# Power_Controller_2_0.net
KiCad netlist of a schematic drawn in EAGLE
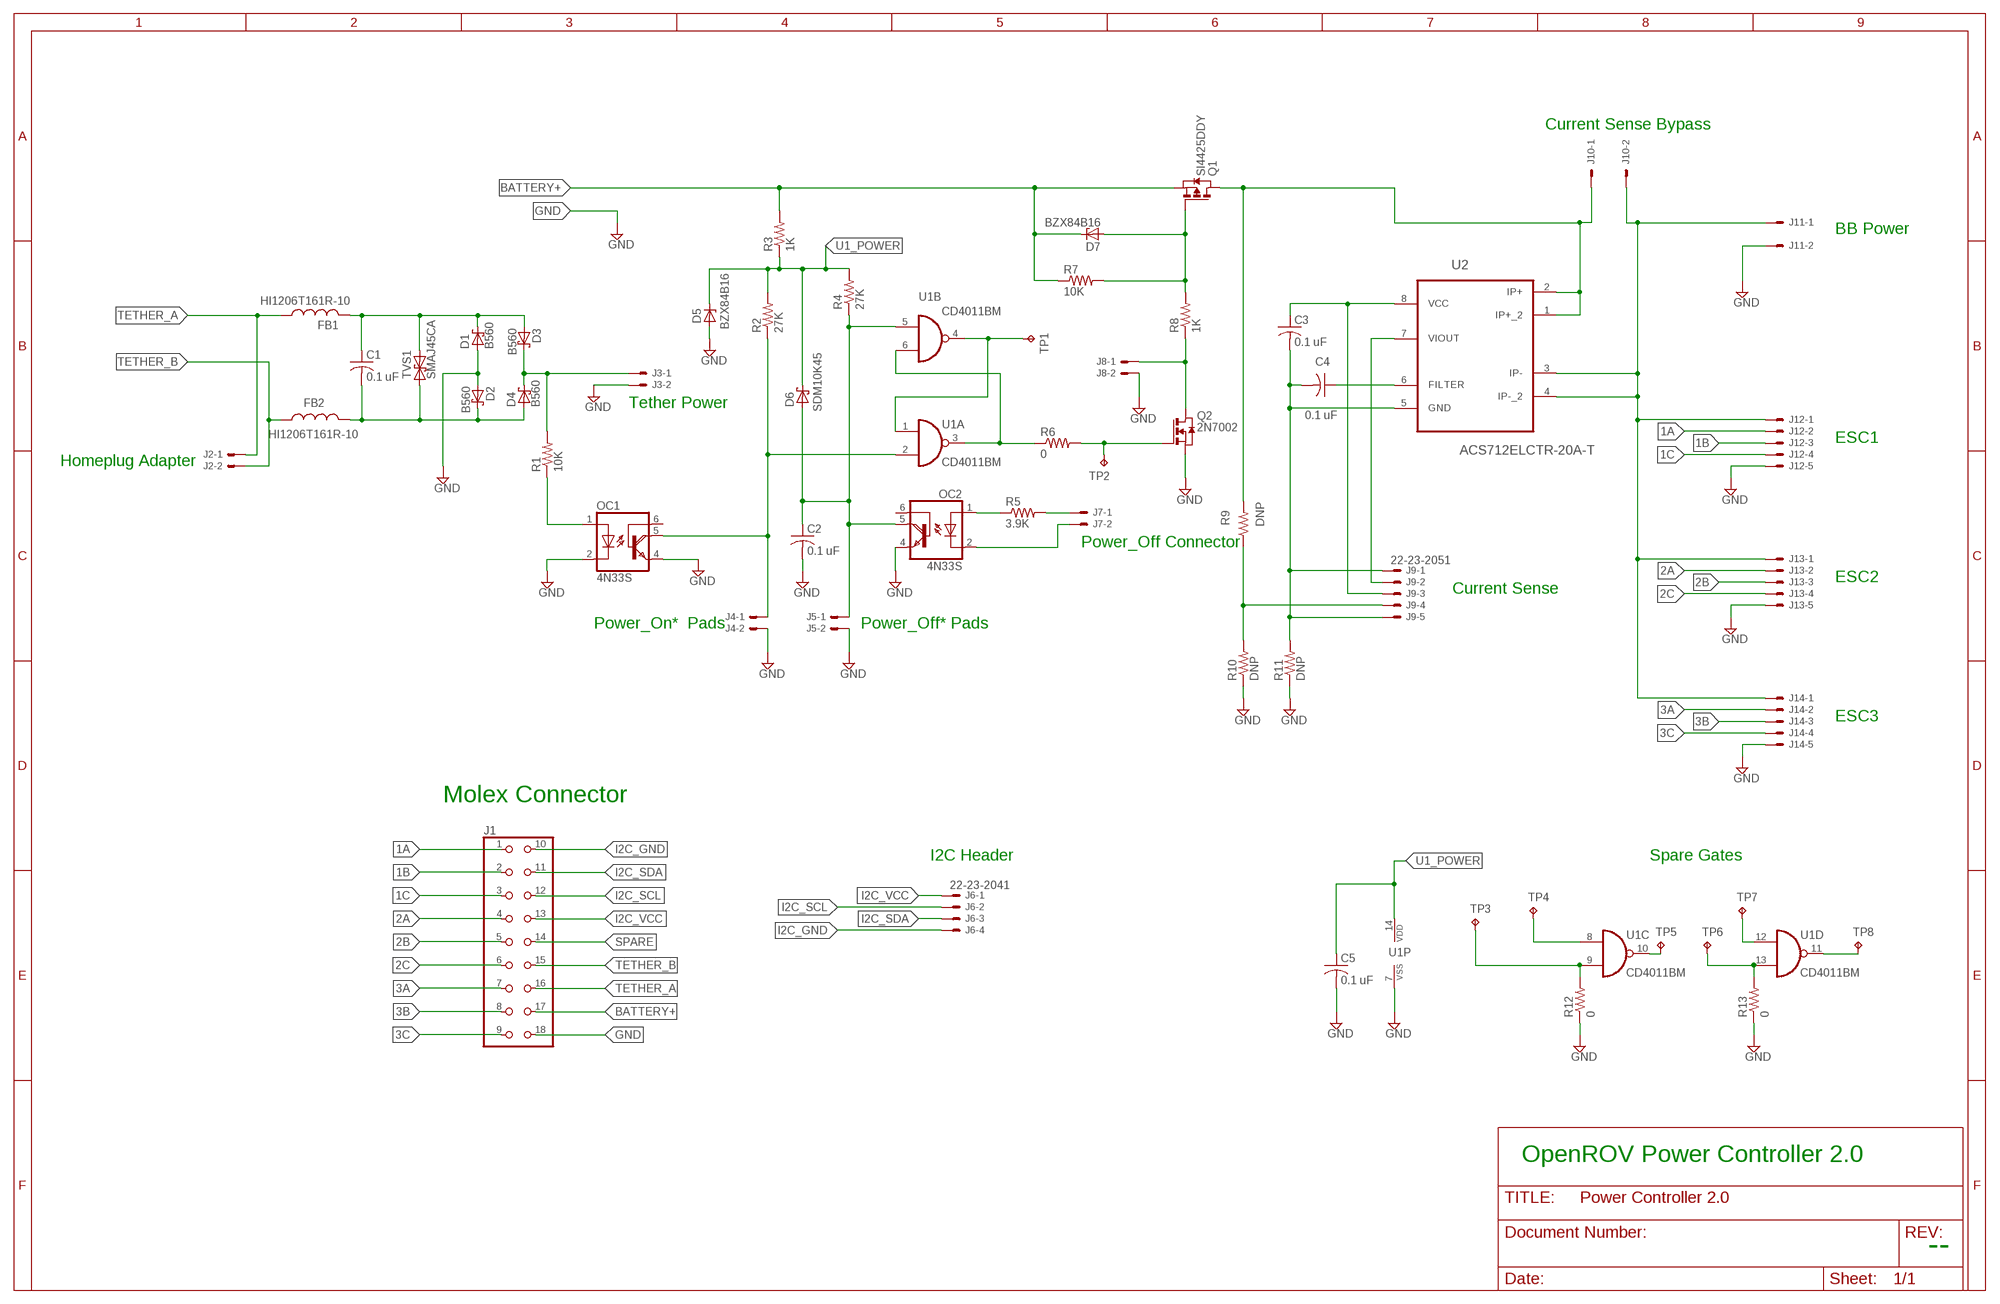
[diagram p0: schematic, sheet 1]

(export (version "E")
  (design (tool "Eeschema 10.0.6"))
  (components
    (comp (ref "C1")
      (value "0.1 uF")
      (footprint "eagle-import:C0805K")
      (libsource (lib "eagle-import") (part "C-USC0805K"))
    )
    (comp (ref "C2")
      (value "0.1 uF")
      (footprint "eagle-import:C0805K")
      (libsource (lib "eagle-import") (part "C-USC0805K"))
    )
    (comp (ref "C3")
      (value "0.1 uF")
      (footprint "eagle-import:C0805K")
      (libsource (lib "eagle-import") (part "C-USC0805K"))
    )
    (comp (ref "C4")
      (value "0.1 uF")
      (footprint "eagle-import:C0805K")
      (libsource (lib "eagle-import") (part "C-USC0805K"))
    )
    (comp (ref "C5")
      (value "0.1 uF")
      (footprint "eagle-import:C0805K")
      (libsource (lib "eagle-import") (part "C-USC0805K"))
    )
    (comp (ref "D1")
      (value "B560")
      (footprint "eagle-import:SMC")
      (libsource (lib "eagle-import") (part "SCHOTTKY-DIODESMC"))
    )
    (comp (ref "D2")
      (value "B560")
      (footprint "eagle-import:SMC")
      (libsource (lib "eagle-import") (part "SCHOTTKY-DIODESMC"))
    )
    (comp (ref "D3")
      (value "B560")
      (footprint "eagle-import:SMC")
      (libsource (lib "eagle-import") (part "SCHOTTKY-DIODESMC"))
    )
    (comp (ref "D4")
      (value "B560")
      (footprint "eagle-import:SMC")
      (libsource (lib "eagle-import") (part "SCHOTTKY-DIODESMC"))
    )
    (comp (ref "D5")
      (value "BZX84B16")
      (footprint "eagle-import:TO236")
      (libsource (lib "eagle-import") (part "BZX84CSMD"))
    )
    (comp (ref "D6")
      (value "SDM10K45")
      (footprint "eagle-import:SOD323")
      (libsource (lib "eagle-import") (part "SCHOTTKYSOD323"))
    )
    (comp (ref "D7")
      (value "BZX84B16")
      (footprint "eagle-import:TO236")
      (libsource (lib "eagle-import") (part "BZX84CSMD"))
    )
    (comp (ref "FB1")
      (value "HI1206T161R-10")
      (footprint "eagle-import:R1206")
      (libsource (lib "eagle-import") (part "FERRITESIZE_1206"))
    )
    (comp (ref "FB2")
      (value "HI1206T161R-10")
      (footprint "eagle-import:R1206")
      (libsource (lib "eagle-import") (part "FERRITESIZE_1206"))
    )
    (comp (ref "J1")
      (value "MINI-FIT-JR-18")
      (footprint "eagle-import:MINI-FIT-JR-18-PEGS")
      (libsource (lib "eagle-import") (part "MINI-FIT-JR-18"))
    )
    (comp (ref "J2")
      (value "22-23-2021")
      (footprint "eagle-import:22-23-2021")
      (fields (field (name "MF") "MOLEX"))
      (libsource (lib "eagle-import") (part "22-23-2021"))
    )
    (comp (ref "J3")
      (value "KK-156-2")
      (footprint "eagle-import:KK-156-2")
      (libsource (lib "eagle-import") (part "KK-156-2"))
    )
    (comp (ref "J4")
      (value "22-23-2021")
      (footprint "eagle-import:22-23-2021")
      (fields (field (name "MF") "MOLEX"))
      (libsource (lib "eagle-import") (part "22-23-2021"))
    )
    (comp (ref "J5")
      (value "22-23-2021")
      (footprint "eagle-import:22-23-2021")
      (fields (field (name "MF") "MOLEX"))
      (libsource (lib "eagle-import") (part "22-23-2021"))
    )
    (comp (ref "J6")
      (value "22-23-2041")
      (footprint "eagle-import:22-23-2041")
      (fields (field (name "MF") "MOLEX"))
      (libsource (lib "eagle-import") (part "22-23-2041"))
    )
    (comp (ref "J7")
      (value "22-23-2021")
      (footprint "eagle-import:22-23-2021")
      (fields (field (name "MF") "MOLEX"))
      (libsource (lib "eagle-import") (part "22-23-2021"))
    )
    (comp (ref "J8")
      (value "22-23-2021")
      (footprint "eagle-import:22-23-2021")
      (fields (field (name "MF") "MOLEX"))
      (libsource (lib "eagle-import") (part "22-23-2021"))
    )
    (comp (ref "J9")
      (value "22-23-2051")
      (footprint "eagle-import:22-23-2051")
      (fields (field (name "MF") "MOLEX"))
      (libsource (lib "eagle-import") (part "22-23-2051"))
    )
    (comp (ref "J10")
      (value "KK-156-2")
      (footprint "eagle-import:KK-156-2")
      (libsource (lib "eagle-import") (part "KK-156-2"))
    )
    (comp (ref "J11")
      (value "KK-156-2")
      (footprint "eagle-import:KK-156-2")
      (libsource (lib "eagle-import") (part "KK-156-2"))
    )
    (comp (ref "J12")
      (value "ESC_PADSCUSTOM")
      (footprint "eagle-import:ESC-PADS")
      (libsource (lib "eagle-import") (part "ESC_PADSCUSTOM"))
    )
    (comp (ref "J13")
      (value "ESC_PADSCUSTOM")
      (footprint "eagle-import:ESC-PADS")
      (libsource (lib "eagle-import") (part "ESC_PADSCUSTOM"))
    )
    (comp (ref "J14")
      (value "ESC_PADSCUSTOM")
      (footprint "eagle-import:ESC-PADS")
      (libsource (lib "eagle-import") (part "ESC_PADSCUSTOM"))
    )
    (comp (ref "OC1")
      (value "4N33S")
      (footprint "eagle-import:DIL6-SMD")
      (libsource (lib "eagle-import") (part "4N33S"))
    )
    (comp (ref "OC2")
      (value "4N33S")
      (footprint "eagle-import:DIL6-SMD")
      (libsource (lib "eagle-import") (part "4N33S"))
    )
    (comp (ref "Q1")
      (value "SI4425DDY")
      (footprint "eagle-import:SO8")
      (libsource (lib "eagle-import") (part "PMOS-SO8"))
    )
    (comp (ref "Q2")
      (value "2N7002")
      (footprint "eagle-import:SOT-23")
      (libsource (lib "eagle-import") (part "NMOSSOT23"))
    )
    (comp (ref "R1")
      (value "10K")
      (footprint "eagle-import:R0805")
      (libsource (lib "eagle-import") (part "R-US_R0805"))
    )
    (comp (ref "R2")
      (value "27K")
      (footprint "eagle-import:R0805")
      (libsource (lib "eagle-import") (part "R-US_R0805"))
    )
    (comp (ref "R3")
      (value "1K")
      (footprint "eagle-import:R0805")
      (libsource (lib "eagle-import") (part "R-US_R0805"))
    )
    (comp (ref "R4")
      (value "27K")
      (footprint "eagle-import:R0805")
      (libsource (lib "eagle-import") (part "R-US_R0805"))
    )
    (comp (ref "R5")
      (value "3.9K")
      (footprint "eagle-import:R0805")
      (libsource (lib "eagle-import") (part "R-US_R0805"))
    )
    (comp (ref "R6")
      (value "0")
      (footprint "eagle-import:R0805")
      (libsource (lib "eagle-import") (part "R-US_R0805"))
    )
    (comp (ref "R7")
      (value "10K")
      (footprint "eagle-import:R0805")
      (libsource (lib "eagle-import") (part "R-US_R0805"))
    )
    (comp (ref "R8")
      (value "1K")
      (footprint "eagle-import:R0805")
      (libsource (lib "eagle-import") (part "R-US_R0805"))
    )
    (comp (ref "R9")
      (value "DNP")
      (footprint "eagle-import:R0805")
      (libsource (lib "eagle-import") (part "R-US_R0805"))
    )
    (comp (ref "R10")
      (value "DNP")
      (footprint "eagle-import:R0805")
      (libsource (lib "eagle-import") (part "R-US_R0805"))
    )
    (comp (ref "R11")
      (value "DNP")
      (footprint "eagle-import:R0805")
      (libsource (lib "eagle-import") (part "R-US_R0805"))
    )
    (comp (ref "R12")
      (value "0")
      (footprint "eagle-import:R0805")
      (libsource (lib "eagle-import") (part "R-US_R0805"))
    )
    (comp (ref "R13")
      (value "0")
      (footprint "eagle-import:R0805")
      (libsource (lib "eagle-import") (part "R-US_R0805"))
    )
    (comp (ref "TP1")
      (value "TPPAD1-13")
      (footprint "eagle-import:P1-13")
      (libsource (lib "eagle-import") (part "TPPAD1-13"))
    )
    (comp (ref "TP2")
      (value "TPPAD1-13")
      (footprint "eagle-import:P1-13")
      (libsource (lib "eagle-import") (part "TPPAD1-13"))
    )
    (comp (ref "TP3")
      (value "TPPAD1-13")
      (footprint "eagle-import:P1-13")
      (libsource (lib "eagle-import") (part "TPPAD1-13"))
    )
    (comp (ref "TP4")
      (value "TPPAD1-13")
      (footprint "eagle-import:P1-13")
      (libsource (lib "eagle-import") (part "TPPAD1-13"))
    )
    (comp (ref "TP5")
      (value "TPPAD1-13")
      (footprint "eagle-import:P1-13")
      (libsource (lib "eagle-import") (part "TPPAD1-13"))
    )
    (comp (ref "TP6")
      (value "TPPAD1-13")
      (footprint "eagle-import:P1-13")
      (libsource (lib "eagle-import") (part "TPPAD1-13"))
    )
    (comp (ref "TP7")
      (value "TPPAD1-13")
      (footprint "eagle-import:P1-13")
      (libsource (lib "eagle-import") (part "TPPAD1-13"))
    )
    (comp (ref "TP8")
      (value "TPPAD1-13")
      (footprint "eagle-import:P1-13")
      (libsource (lib "eagle-import") (part "TPPAD1-13"))
    )
    (comp (ref "TVS1")
      (value "SMAJ45CA")
      (footprint "eagle-import:DO214AC")
      (libsource (lib "eagle-import") (part "TVS-BIDIRDO214-AC"))
    )
    (comp (ref "U1")
      (value "CD4011BM")
      (footprint "eagle-import:SO14")
      (libsource (lib "eagle-import") (part "4011D"))
    )
    (comp (ref "U2")
      (value "ACS712ELCTR-20A-T")
      (footprint "eagle-import:SOIC127P600X175-8N")
      (libsource (lib "eagle-import") (part "ACS712ELCTR-20A-T"))
    )
  )
  (nets
    (net (code "1") (name "1A") (class "Default")
      (node (ref "J1") (pin "1") (pinfunction "1_1") (pintype "passive"))
      (node (ref "J12") (pin "2") (pinfunction "S_2") (pintype "passive"))
    )
    (net (code "2") (name "1B") (class "Default")
      (node (ref "J1") (pin "2") (pinfunction "2_2") (pintype "passive"))
      (node (ref "J12") (pin "3") (pinfunction "S_3") (pintype "passive"))
    )
    (net (code "3") (name "1C") (class "Default")
      (node (ref "J1") (pin "3") (pinfunction "3_3") (pintype "passive"))
      (node (ref "J12") (pin "4") (pinfunction "S_4") (pintype "passive"))
    )
    (net (code "4") (name "2A") (class "Default")
      (node (ref "J1") (pin "4") (pinfunction "4_4") (pintype "passive"))
      (node (ref "J13") (pin "2") (pinfunction "S_2") (pintype "passive"))
    )
    (net (code "5") (name "2B") (class "Default")
      (node (ref "J1") (pin "5") (pinfunction "5_5") (pintype "passive"))
      (node (ref "J13") (pin "3") (pinfunction "S_3") (pintype "passive"))
    )
    (net (code "6") (name "2C") (class "Default")
      (node (ref "J1") (pin "6") (pinfunction "6_6") (pintype "passive"))
      (node (ref "J13") (pin "4") (pinfunction "S_4") (pintype "passive"))
    )
    (net (code "7") (name "3A") (class "Default")
      (node (ref "J1") (pin "7") (pinfunction "7_7") (pintype "passive"))
      (node (ref "J14") (pin "2") (pinfunction "S_2") (pintype "passive"))
    )
    (net (code "8") (name "3B") (class "Default")
      (node (ref "J1") (pin "8") (pinfunction "8_8") (pintype "passive"))
      (node (ref "J14") (pin "3") (pinfunction "S_3") (pintype "passive"))
    )
    (net (code "9") (name "3C") (class "Default")
      (node (ref "J1") (pin "9") (pinfunction "9_9") (pintype "passive"))
      (node (ref "J14") (pin "4") (pinfunction "S_4") (pintype "passive"))
    )
    (net (code "10") (name "BATTERY+") (class "Default")
      (node (ref "D7") (pin "C") (pinfunction "C_C") (pintype "passive"))
      (node (ref "J1") (pin "17") (pinfunction "17_17") (pintype "passive"))
      (node (ref "Q1") (pin "1") (pinfunction "S_1") (pintype "passive"))
      (node (ref "Q1") (pin "2") (pinfunction "S_2") (pintype "passive"))
      (node (ref "Q1") (pin "3") (pinfunction "S_3") (pintype "passive"))
      (node (ref "R3") (pin "2") (pinfunction "2_2") (pintype "passive"))
      (node (ref "R7") (pin "1") (pinfunction "1_1") (pintype "passive"))
    )
    (net (code "11") (name "GND") (class "Default")
      (node (ref "C2") (pin "2") (pinfunction "2_2") (pintype "passive"))
      (node (ref "C5") (pin "2") (pinfunction "2_2") (pintype "passive"))
      (node (ref "D1") (pin "A") (pinfunction "A_A") (pintype "passive"))
      (node (ref "D2") (pin "A") (pinfunction "A_A") (pintype "passive"))
      (node (ref "D5") (pin "A") (pinfunction "A_A") (pintype "passive"))
      (node (ref "J1") (pin "18") (pinfunction "18_18") (pintype "passive"))
      (node (ref "J11") (pin "2") (pinfunction "S_2") (pintype "passive"))
      (node (ref "J12") (pin "5") (pinfunction "S_5") (pintype "passive"))
      (node (ref "J13") (pin "5") (pinfunction "S_5") (pintype "passive"))
      (node (ref "J14") (pin "5") (pinfunction "S_5") (pintype "passive"))
      (node (ref "J3") (pin "2") (pinfunction "S_2") (pintype "passive"))
      (node (ref "J4") (pin "2") (pinfunction "S_2") (pintype "passive"))
      (node (ref "J5") (pin "2") (pinfunction "S_2") (pintype "passive"))
      (node (ref "J8") (pin "2") (pinfunction "S_2") (pintype "passive"))
      (node (ref "OC1") (pin "2") (pinfunction "C_2") (pintype "passive"))
      (node (ref "OC1") (pin "4") (pinfunction "E_4") (pintype "passive"))
      (node (ref "OC2") (pin "4") (pinfunction "E_4") (pintype "passive"))
      (node (ref "Q2") (pin "2") (pinfunction "S_2") (pintype "passive"))
      (node (ref "R10") (pin "1") (pinfunction "1_1") (pintype "passive"))
      (node (ref "R11") (pin "1") (pinfunction "1_1") (pintype "passive"))
      (node (ref "R12") (pin "1") (pinfunction "1_1") (pintype "passive"))
      (node (ref "R13") (pin "1") (pinfunction "1_1") (pintype "passive"))
      (node (ref "U1") (pin "7") (pinfunction "VSS_7") (pintype "power_in"))
    )
    (net (code "12") (name "I2C_GND") (class "Default")
      (node (ref "J1") (pin "10") (pinfunction "10_10") (pintype "passive"))
      (node (ref "J6") (pin "4") (pinfunction "S_4") (pintype "passive"))
    )
    (net (code "13") (name "I2C_SCL") (class "Default")
      (node (ref "J1") (pin "12") (pinfunction "12_12") (pintype "passive"))
      (node (ref "J6") (pin "2") (pinfunction "S_2") (pintype "passive"))
    )
    (net (code "14") (name "I2C_SDA") (class "Default")
      (node (ref "J1") (pin "11") (pinfunction "11_11") (pintype "passive"))
      (node (ref "J6") (pin "3") (pinfunction "S_3") (pintype "passive"))
    )
    (net (code "15") (name "I2C_VCC") (class "Default")
      (node (ref "J1") (pin "13") (pinfunction "13_13") (pintype "passive"))
      (node (ref "J6") (pin "1") (pinfunction "S_1") (pintype "passive"))
    )
    (net (code "16") (name "Net-(D6-A)") (class "Default")
      (node (ref "C2") (pin "1") (pinfunction "1_1") (pintype "passive"))
      (node (ref "D6") (pin "2") (pinfunction "A_2") (pintype "passive"))
      (node (ref "J5") (pin "1") (pinfunction "S_1") (pintype "passive"))
      (node (ref "OC2") (pin "5") (pinfunction "COL_5") (pintype "passive"))
      (node (ref "R4") (pin "1") (pinfunction "1_1") (pintype "passive"))
      (node (ref "U1") (pin "5") (pinfunction "I0_5") (pintype "input"))
    )
    (net (code "17") (name "Net-(J3A-S)") (class "Default")
      (node (ref "D3") (pin "C") (pinfunction "C_C") (pintype "passive"))
      (node (ref "D4") (pin "C") (pinfunction "C_C") (pintype "passive"))
      (node (ref "J3") (pin "1") (pinfunction "S_1") (pintype "passive"))
      (node (ref "R1") (pin "2") (pinfunction "2_2") (pintype "passive"))
    )
    (net (code "18") (name "Net-(J4A-S)") (class "Default")
      (node (ref "J4") (pin "1") (pinfunction "S_1") (pintype "passive"))
      (node (ref "OC1") (pin "5") (pinfunction "COL_5") (pintype "passive"))
      (node (ref "R2") (pin "1") (pinfunction "1_1") (pintype "passive"))
      (node (ref "U1") (pin "2") (pinfunction "I1_2") (pintype "input"))
    )
    (net (code "19") (name "Net-(J7A-S)") (class "Default")
      (node (ref "J7") (pin "1") (pinfunction "S_1") (pintype "passive"))
      (node (ref "R5") (pin "2") (pinfunction "2_2") (pintype "passive"))
    )
    (net (code "20") (name "Net-(J7B-S)") (class "Default")
      (node (ref "J7") (pin "2") (pinfunction "S_2") (pintype "passive"))
      (node (ref "OC2") (pin "2") (pinfunction "C_2") (pintype "passive"))
    )
    (net (code "21") (name "Net-(J8A-S)") (class "Default")
      (node (ref "J8") (pin "1") (pinfunction "S_1") (pintype "passive"))
      (node (ref "Q2") (pin "1") (pinfunction "D_1") (pintype "passive"))
      (node (ref "R8") (pin "1") (pinfunction "1_1") (pintype "passive"))
    )
    (net (code "22") (name "Net-(J9A-S)") (class "Default")
      (node (ref "C3") (pin "2") (pinfunction "2_2") (pintype "passive"))
      (node (ref "C4") (pin "2") (pinfunction "2_2") (pintype "passive"))
      (node (ref "J9") (pin "1") (pinfunction "S_1") (pintype "passive"))
      (node (ref "J9") (pin "5") (pinfunction "S_5") (pintype "passive"))
      (node (ref "R11") (pin "2") (pinfunction "2_2") (pintype "passive"))
      (node (ref "U2") (pin "5") (pinfunction "GND_5") (pintype "passive"))
    )
    (net (code "23") (name "Net-(J9B-S)") (class "Default")
      (node (ref "J9") (pin "2") (pinfunction "S_2") (pintype "passive"))
      (node (ref "U2") (pin "7") (pinfunction "VIOUT_7") (pintype "output"))
    )
    (net (code "24") (name "Net-(J9C-S)") (class "Default")
      (node (ref "C3") (pin "1") (pinfunction "1_1") (pintype "passive"))
      (node (ref "J9") (pin "3") (pinfunction "S_3") (pintype "passive"))
      (node (ref "U2") (pin "8") (pinfunction "VCC_8") (pintype "power_in"))
    )
    (net (code "25") (name "Net-(J9D-S)") (class "Default")
      (node (ref "J9") (pin "4") (pinfunction "S_4") (pintype "passive"))
      (node (ref "R10") (pin "2") (pinfunction "2_2") (pintype "passive"))
      (node (ref "R9") (pin "1") (pinfunction "1_1") (pintype "passive"))
    )
    (net (code "26") (name "Net-(J10A-S)") (class "Default")
      (node (ref "J10") (pin "1") (pinfunction "S_1") (pintype "passive"))
      (node (ref "Q1") (pin "5") (pinfunction "D_5") (pintype "passive"))
      (node (ref "Q1") (pin "6") (pinfunction "D_6") (pintype "passive"))
      (node (ref "Q1") (pin "7") (pinfunction "D_7") (pintype "passive"))
      (node (ref "Q1") (pin "8") (pinfunction "D_8") (pintype "passive"))
      (node (ref "R9") (pin "2") (pinfunction "2_2") (pintype "passive"))
      (node (ref "U2") (pin "1") (pinfunction "IP+_2_1") (pintype "input"))
      (node (ref "U2") (pin "2") (pinfunction "IP+_2") (pintype "input"))
    )
    (net (code "27") (name "Net-(J10B-S)") (class "Default")
      (node (ref "J10") (pin "2") (pinfunction "S_2") (pintype "passive"))
      (node (ref "J11") (pin "1") (pinfunction "S_1") (pintype "passive"))
      (node (ref "J12") (pin "1") (pinfunction "S_1") (pintype "passive"))
      (node (ref "J13") (pin "1") (pinfunction "S_1") (pintype "passive"))
      (node (ref "J14") (pin "1") (pinfunction "S_1") (pintype "passive"))
      (node (ref "U2") (pin "3") (pinfunction "IP-_3") (pintype "input"))
      (node (ref "U2") (pin "4") (pinfunction "IP-_2_4") (pintype "input"))
    )
    (net (code "28") (name "Net-(OC1-A)") (class "Default")
      (node (ref "OC1") (pin "1") (pinfunction "A_1") (pintype "passive"))
      (node (ref "R1") (pin "1") (pinfunction "1_1") (pintype "passive"))
    )
    (net (code "29") (name "Net-(OC2-A)") (class "Default")
      (node (ref "OC2") (pin "1") (pinfunction "A_1") (pintype "passive"))
      (node (ref "R5") (pin "1") (pinfunction "1_1") (pintype "passive"))
    )
    (net (code "30") (name "Net-(Q1-G)") (class "Default")
      (node (ref "D7") (pin "A") (pinfunction "A_A") (pintype "passive"))
      (node (ref "Q1") (pin "4") (pinfunction "G_4") (pintype "passive"))
      (node (ref "R7") (pin "2") (pinfunction "2_2") (pintype "passive"))
      (node (ref "R8") (pin "2") (pinfunction "2_2") (pintype "passive"))
    )
    (net (code "31") (name "Net-(Q2-G)") (class "Default")
      (node (ref "Q2") (pin "3") (pinfunction "G_3") (pintype "passive"))
      (node (ref "R6") (pin "2") (pinfunction "2_2") (pintype "passive"))
      (node (ref "TP2") (pin "TP") (pinfunction "TP_TP") (pintype "input"))
    )
    (net (code "32") (name "Net-(TVS1-1)") (class "Default")
      (node (ref "C1") (pin "2") (pinfunction "2_2") (pintype "passive"))
      (node (ref "D2") (pin "C") (pinfunction "C_C") (pintype "passive"))
      (node (ref "D4") (pin "A") (pinfunction "A_A") (pintype "passive"))
      (node (ref "FB2") (pin "2") (pinfunction "2_2") (pintype "passive"))
      (node (ref "TVS1") (pin "A") (pinfunction "1_A") (pintype "passive"))
    )
    (net (code "33") (name "Net-(TVS1-2)") (class "Default")
      (node (ref "C1") (pin "1") (pinfunction "1_1") (pintype "passive"))
      (node (ref "D1") (pin "C") (pinfunction "C_C") (pintype "passive"))
      (node (ref "D3") (pin "A") (pinfunction "A_A") (pintype "passive"))
      (node (ref "FB1") (pin "2") (pinfunction "2_2") (pintype "passive"))
      (node (ref "TVS1") (pin "C") (pinfunction "2_C") (pintype "passive"))
    )
    (net (code "34") (name "Net-(U1A-I0)") (class "Default")
      (node (ref "TP1") (pin "TP") (pinfunction "TP_TP") (pintype "input"))
      (node (ref "U1") (pin "1") (pinfunction "I0_1") (pintype "input"))
      (node (ref "U1") (pin "4") (pinfunction "O_4") (pintype "output"))
    )
    (net (code "35") (name "Net-(U1A-O)") (class "Default")
      (node (ref "R6") (pin "1") (pinfunction "1_1") (pintype "passive"))
      (node (ref "U1") (pin "3") (pinfunction "O_3") (pintype "output"))
      (node (ref "U1") (pin "6") (pinfunction "I1_6") (pintype "input"))
    )
    (net (code "36") (name "Net-(U1C-I0)") (class "Default")
      (node (ref "TP4") (pin "TP") (pinfunction "TP_TP") (pintype "input"))
      (node (ref "U1") (pin "8") (pinfunction "I0_8") (pintype "input"))
    )
    (net (code "37") (name "Net-(U1C-I1)") (class "Default")
      (node (ref "R12") (pin "2") (pinfunction "2_2") (pintype "passive"))
      (node (ref "TP3") (pin "TP") (pinfunction "TP_TP") (pintype "input"))
      (node (ref "U1") (pin "9") (pinfunction "I1_9") (pintype "input"))
    )
    (net (code "38") (name "Net-(U1C-O)") (class "Default")
      (node (ref "TP5") (pin "TP") (pinfunction "TP_TP") (pintype "input"))
      (node (ref "U1") (pin "10") (pinfunction "O_10") (pintype "output"))
    )
    (net (code "39") (name "Net-(U1D-I0)") (class "Default")
      (node (ref "TP7") (pin "TP") (pinfunction "TP_TP") (pintype "input"))
      (node (ref "U1") (pin "12") (pinfunction "I0_12") (pintype "input"))
    )
    (net (code "40") (name "Net-(U1D-I1)") (class "Default")
      (node (ref "R13") (pin "2") (pinfunction "2_2") (pintype "passive"))
      (node (ref "TP6") (pin "TP") (pinfunction "TP_TP") (pintype "input"))
      (node (ref "U1") (pin "13") (pinfunction "I1_13") (pintype "input"))
    )
    (net (code "41") (name "Net-(U1D-O)") (class "Default")
      (node (ref "TP8") (pin "TP") (pinfunction "TP_TP") (pintype "input"))
      (node (ref "U1") (pin "11") (pinfunction "O_11") (pintype "output"))
    )
    (net (code "42") (name "Net-(U2-FILTER)") (class "Default")
      (node (ref "C4") (pin "1") (pinfunction "1_1") (pintype "passive"))
      (node (ref "U2") (pin "6") (pinfunction "FILTER_6") (pintype "input"))
    )
    (net (code "43") (name "SPARE") (class "Default")
      (node (ref "J1") (pin "14") (pinfunction "14_14") (pintype "passive"))
    )
    (net (code "44") (name "TETHER_A") (class "Default")
      (node (ref "FB1") (pin "1") (pinfunction "1_1") (pintype "passive"))
      (node (ref "J1") (pin "16") (pinfunction "16_16") (pintype "passive"))
      (node (ref "J2") (pin "1") (pinfunction "S_1") (pintype "passive"))
    )
    (net (code "45") (name "TETHER_B") (class "Default")
      (node (ref "FB2") (pin "1") (pinfunction "1_1") (pintype "passive"))
      (node (ref "J1") (pin "15") (pinfunction "15_15") (pintype "passive"))
      (node (ref "J2") (pin "2") (pinfunction "S_2") (pintype "passive"))
    )
    (net (code "46") (name "U1_POWER") (class "Default")
      (node (ref "C5") (pin "1") (pinfunction "1_1") (pintype "passive"))
      (node (ref "D5") (pin "C") (pinfunction "C_C") (pintype "passive"))
      (node (ref "D6") (pin "1") (pinfunction "C_1") (pintype "passive"))
      (node (ref "R2") (pin "2") (pinfunction "2_2") (pintype "passive"))
      (node (ref "R3") (pin "1") (pinfunction "1_1") (pintype "passive"))
      (node (ref "R4") (pin "2") (pinfunction "2_2") (pintype "passive"))
      (node (ref "U1") (pin "14") (pinfunction "VDD_14") (pintype "power_in"))
    )
    (net (code "47") (name "unconnected-(OC1-B-Pad6)") (class "Default")
      (node (ref "OC1") (pin "6") (pinfunction "B_6") (pintype "passive"))
    )
    (net (code "48") (name "unconnected-(OC2-B-Pad6)") (class "Default")
      (node (ref "OC2") (pin "6") (pinfunction "B_6") (pintype "passive"))
    )
  )
)
